# Morpheus_LED1.net
KiCad netlist of a schematic drawn in Altium Designer
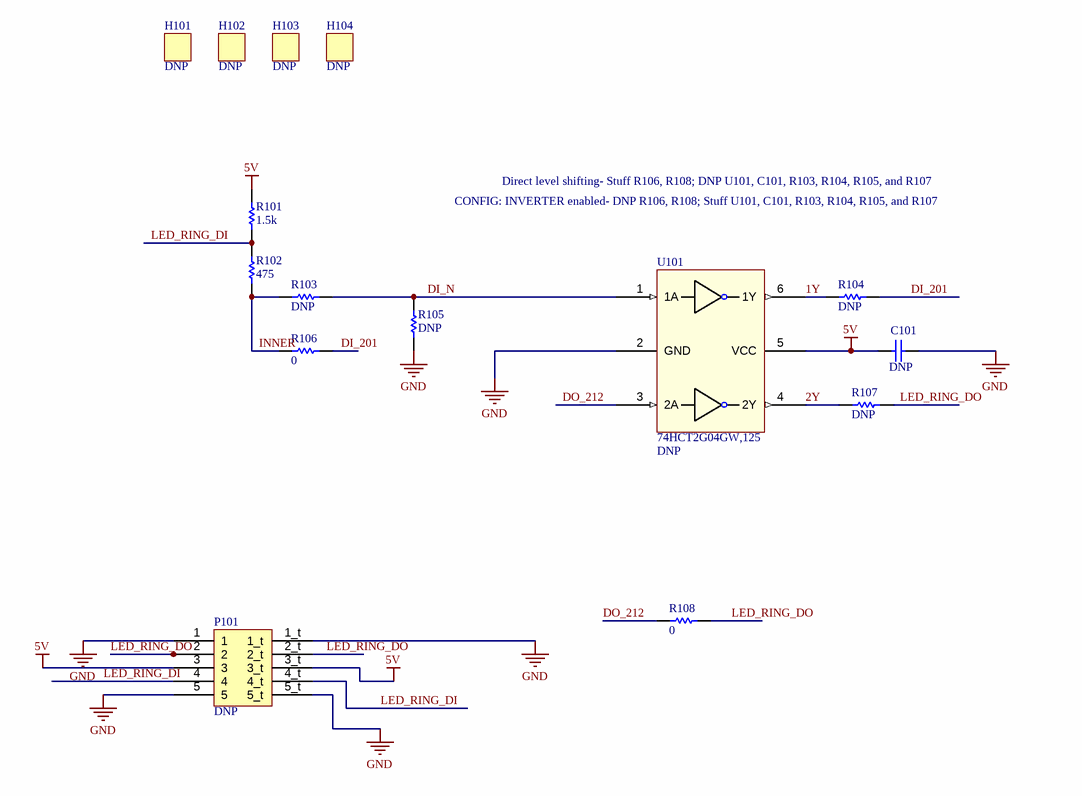
[diagram p0: Morpheus_LED1.SchDoc]

(export (version "E")
  (design (tool "Eeschema 10.0.6"))
  (components
    (comp (ref "C101")
      (value "DNP")
      (footprint "CAP0402_SENSE_DVT")
      (description "Chip capacitor")
      (fields (field (name "TOLERANCE") "10%") (field (name "VOLTAGE") "50V"))
      (libsource (lib "Hello") (part "C_0.1u_10_50_X7R_0402"))
    )
    (comp (ref "H101")
      (value "DNP")
      (footprint "HOLE_ROUND_1.4mm")
      (description "general purpose hole")
      (libsource (lib "Hello") (part "Hole"))
    )
    (comp (ref "H102")
      (value "DNP")
      (footprint "HOLE_ROUND_1.4mm")
      (description "general purpose hole")
      (libsource (lib "Hello") (part "Hole"))
    )
    (comp (ref "H103")
      (value "DNP")
      (footprint "HOLE_ROUND_1.4mm")
      (description "general purpose hole")
      (libsource (lib "Hello") (part "Hole"))
    )
    (comp (ref "H104")
      (value "DNP")
      (footprint "HOLE_ROUND_1.4mm")
      (description "general purpose hole")
      (libsource (lib "Hello") (part "Hole"))
    )
    (comp (ref "P101")
      (value "DNP")
      (footprint "mate_for_molex_51281-0594")
      (description "Molex 5-pin flex connector 0.3mm working height")
      (libsource (lib "Hello") (part "mate_for_molex_51281-0594"))
    )
    (comp (ref "R101")
      (value "1.5k")
      (footprint "RES0402_SENSE_DVT")
      (description "Chip Resistor")
      (fields (field (name "TOLERANCE") "5 %") (field (name "POWER") "0.1 W"))
      (libsource (lib "Hello") (part "R_1.5k_5_0.1_0402"))
    )
    (comp (ref "R102")
      (value "475")
      (footprint "RES0402_SENSE_DVT")
      (description "Chip Resistor")
      (fields (field (name "TOLERANCE") "1 %") (field (name "POWER") "0.1 W"))
      (libsource (lib "Hello") (part "R_475_1_0.1_0402"))
    )
    (comp (ref "R103")
      (value "DNP")
      (footprint "RES0402_SENSE_DVT")
      (description "Chip Resistor")
      (fields (field (name "TOLERANCE") "Jumper") (field (name "POWER") "0.1 W"))
      (libsource (lib "Hello") (part "R_0_jumper_0.1_0402"))
    )
    (comp (ref "R104")
      (value "DNP")
      (footprint "RES0402_SENSE_DVT")
      (description "Chip Resistor")
      (fields (field (name "TOLERANCE") "1 %") (field (name "POWER") "0.1 W"))
      (libsource (lib "Hello") (part "R_100_1_0.1_0402"))
    )
    (comp (ref "R105")
      (value "DNP")
      (footprint "RES0402_SENSE_DVT")
      (description "Chip Resistor")
      (fields (field (name "TOLERANCE") "5 %") (field (name "POWER") "0.1 W"))
      (libsource (lib "Hello") (part "R_1.5k_5_0.1_0402"))
    )
    (comp (ref "R106")
      (value "0")
      (footprint "RES0402_SENSE_DVT")
      (description "Chip Resistor")
      (fields (field (name "TOLERANCE") "Jumper") (field (name "POWER") "0.1 W"))
      (libsource (lib "Hello") (part "R_0_jumper_0.1_0402"))
    )
    (comp (ref "R107")
      (value "DNP")
      (footprint "RES0402_SENSE_DVT")
      (description "Chip Resistor")
      (fields (field (name "TOLERANCE") "1 %") (field (name "POWER") "0.1 W"))
      (libsource (lib "Hello") (part "R_100_1_0.1_0402"))
    )
    (comp (ref "R108")
      (value "0")
      (footprint "RES0402_SENSE_DVT")
      (description "Chip Resistor")
      (fields (field (name "TOLERANCE") "Jumper") (field (name "POWER") "0.1 W"))
      (libsource (lib "Hello") (part "R_0_jumper_0.1_0402"))
    )
    (comp (ref "U101")
      (value "DNP")
      (footprint "SOT65P210X110-6N")
      (description "Dual inverter The 74HC2G04; 74HCT2G04 is a high-speed Si-gate CMOS device.")
      (fields (field (name "PN") "74HCT2G04GW,125"))
      (libsource (lib "Hello") (part "74HCT2G04"))
    )
  )
  (nets
    (net (code "1") (name "/1Y") (class "Default")
      (node (ref "R104") (pin "1") (pinfunction "1_1") (pintype "passive"))
      (node (ref "U101") (pin "6") (pinfunction "1Y_6") (pintype "output"))
    )
    (net (code "2") (name "/2Y") (class "Default")
      (node (ref "R107") (pin "1") (pinfunction "1_1") (pintype "passive"))
      (node (ref "U101") (pin "4") (pinfunction "2Y_4") (pintype "output"))
    )
    (net (code "3") (name "/DI_201") (class "Default")
      (node (ref "R104") (pin "2") (pinfunction "2_2") (pintype "passive"))
      (node (ref "R106") (pin "2") (pinfunction "2_2") (pintype "passive"))
    )
    (net (code "4") (name "/DI_N") (class "Default")
      (node (ref "R103") (pin "2") (pinfunction "2_2") (pintype "passive"))
      (node (ref "R105") (pin "2") (pinfunction "2_2") (pintype "passive"))
      (node (ref "U101") (pin "1") (pinfunction "1A_1") (pintype "input"))
    )
    (net (code "5") (name "/DO_212") (class "Default")
      (node (ref "R108") (pin "1") (pinfunction "1_1") (pintype "passive"))
      (node (ref "U101") (pin "3") (pinfunction "2A_3") (pintype "input"))
    )
    (net (code "6") (name "/INNER") (class "Default")
      (node (ref "R102") (pin "1") (pinfunction "1_1") (pintype "passive"))
      (node (ref "R103") (pin "1") (pinfunction "1_1") (pintype "passive"))
      (node (ref "R106") (pin "1") (pinfunction "1_1") (pintype "passive"))
    )
    (net (code "7") (name "/LED_RING_DI") (class "Default")
      (node (ref "P101") (pin "4") (pinfunction "4_4") (pintype "passive"))
      (node (ref "P101") (pin "4_t") (pinfunction "4_t_4_t") (pintype "passive"))
      (node (ref "R101") (pin "1") (pinfunction "1_1") (pintype "passive"))
      (node (ref "R102") (pin "2") (pinfunction "2_2") (pintype "passive"))
    )
    (net (code "8") (name "/LED_RING_DO") (class "Default")
      (node (ref "P101") (pin "2") (pinfunction "2_2") (pintype "passive"))
      (node (ref "P101") (pin "2_t") (pinfunction "2_t_2_t") (pintype "passive"))
      (node (ref "R107") (pin "2") (pinfunction "2_2") (pintype "passive"))
      (node (ref "R108") (pin "2") (pinfunction "2_2") (pintype "passive"))
    )
    (net (code "9") (name "5V") (class "Default")
      (node (ref "C101") (pin "1") (pinfunction "1_1") (pintype "passive"))
      (node (ref "P101") (pin "3") (pinfunction "3_3") (pintype "passive"))
      (node (ref "P101") (pin "3_t") (pinfunction "3_t_3_t") (pintype "passive"))
      (node (ref "R101") (pin "2") (pinfunction "2_2") (pintype "passive"))
      (node (ref "U101") (pin "5") (pinfunction "VCC_5") (pintype "power_in"))
    )
    (net (code "10") (name "GND") (class "Default")
      (node (ref "C101") (pin "2") (pinfunction "2_2") (pintype "passive"))
      (node (ref "P101") (pin "1") (pinfunction "1_1") (pintype "passive"))
      (node (ref "P101") (pin "1_t") (pinfunction "1_t_1_t") (pintype "passive"))
      (node (ref "P101") (pin "5") (pinfunction "5_5") (pintype "passive"))
      (node (ref "P101") (pin "5_t") (pinfunction "5_t_5_t") (pintype "passive"))
      (node (ref "R105") (pin "1") (pinfunction "1_1") (pintype "passive"))
      (node (ref "U101") (pin "2") (pinfunction "GND_2") (pintype "power_in"))
    )
  )
)
